# protection_and_ch.net
KiCad netlist of a schematic drawn in EAGLE
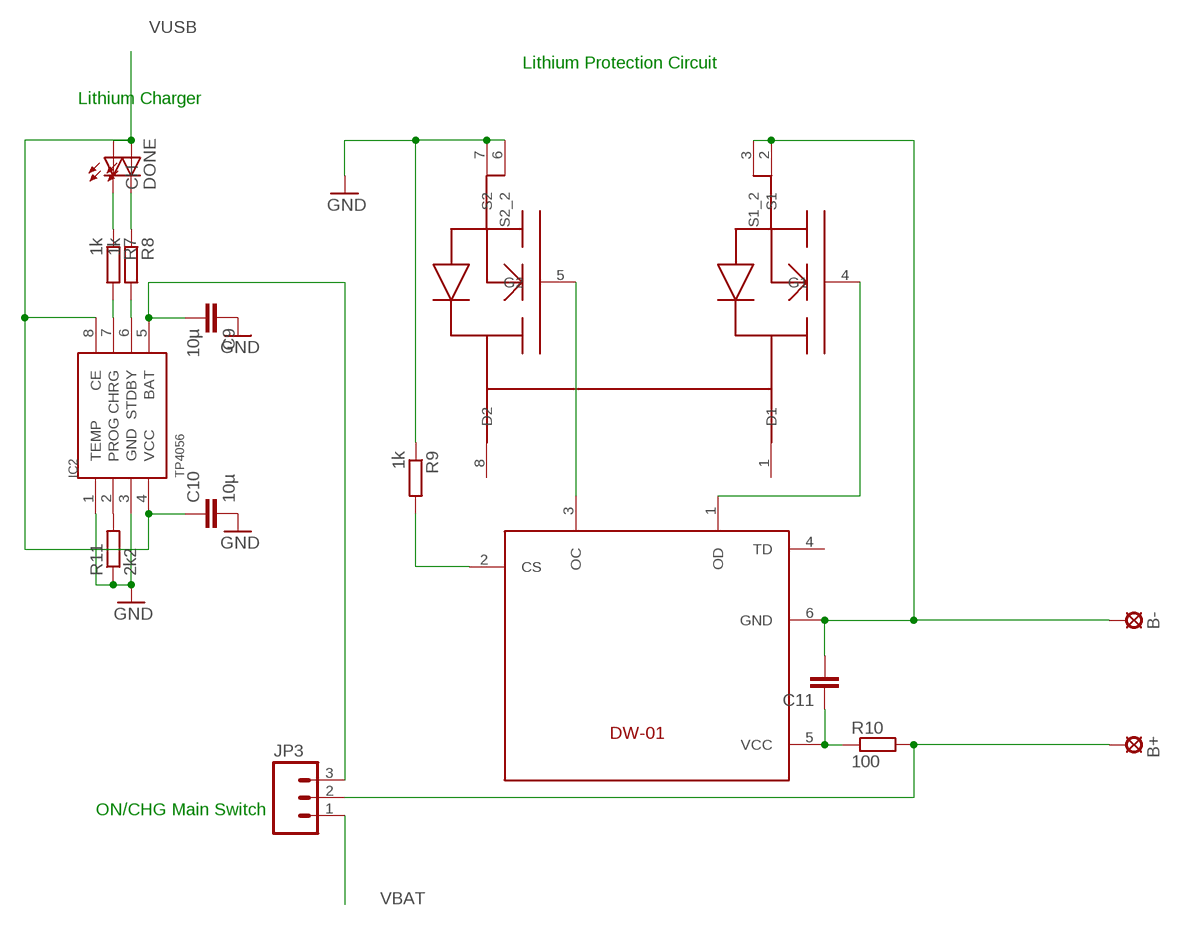
[diagram p0: schematic, sheet 1]

(export (version "E")
  (design (tool "Eeschema 10.0.6"))
  (components
    (comp (ref "B+")
      (value "LSP10")
      (footprint "eagle-import:LSP10")
      (libsource (lib "eagle-import") (part "LSP10"))
    )
    (comp (ref "B-")
      (value "LSP10")
      (footprint "eagle-import:LSP10")
      (libsource (lib "eagle-import") (part "LSP10"))
    )
    (comp (ref "C9")
      (value "10µ")
      (footprint "eagle-import:C0805K")
      (libsource (lib "eagle-import") (part "C-EUC0805K"))
    )
    (comp (ref "C10")
      (value "10µ")
      (footprint "eagle-import:C0805K")
      (libsource (lib "eagle-import") (part "C-EUC0805K"))
    )
    (comp (ref "C11")
      (value "C-EUC0603")
      (footprint "eagle-import:C0603")
      (libsource (lib "eagle-import") (part "C-EUC0603"))
    )
    (comp (ref "CH")
      (value "LEDCHIP-LED0805")
      (footprint "eagle-import:CHIP-LED0805")
      (libsource (lib "eagle-import") (part "LEDCHIP-LED0805"))
    )
    (comp (ref "DONE")
      (value "LEDCHIP-LED0805")
      (footprint "eagle-import:CHIP-LED0805")
      (libsource (lib "eagle-import") (part "LEDCHIP-LED0805"))
    )
    (comp (ref "IC2")
      (value "TP4056")
      (footprint "eagle-import:SOP-8")
      (libsource (lib "eagle-import") (part "TP4056"))
    )
    (comp (ref "JP3")
      (value "M03PTH")
      (footprint "eagle-import:1X03")
      (libsource (lib "eagle-import") (part "M03PTH"))
    )
    (comp (ref "R7")
      (value "1k")
      (footprint "eagle-import:R0603")
      (libsource (lib "eagle-import") (part "R-EU_R0603"))
    )
    (comp (ref "R8")
      (value "1k")
      (footprint "eagle-import:R0603")
      (libsource (lib "eagle-import") (part "R-EU_R0603"))
    )
    (comp (ref "R9")
      (value "1k")
      (footprint "eagle-import:R0603")
      (libsource (lib "eagle-import") (part "R-EU_R0603"))
    )
    (comp (ref "R10")
      (value "100")
      (footprint "eagle-import:R0603")
      (libsource (lib "eagle-import") (part "R-EU_R0603"))
    )
    (comp (ref "R11")
      (value "2k2")
      (footprint "eagle-import:R0603")
      (libsource (lib "eagle-import") (part "R-EU_R0603"))
    )
    (comp (ref "U$1")
      (value "DW-01")
      (footprint "eagle-import:SOT23-6")
      (libsource (lib "eagle-import") (part "DW-01"))
    )
    (comp (ref "U$4")
      (value "8205A")
      (footprint "eagle-import:TSSOP8")
      (libsource (lib "eagle-import") (part "8205A"))
    )
  )
  (nets
    (net (code "1") (name "/VBAT") (class "Default")
      (node (ref "B+") (pin "MP") (pinfunction "MP_MP") (pintype "passive"))
      (node (ref "JP3") (pin "1") (pinfunction "1_1") (pintype "passive"))
      (node (ref "JP3") (pin "2") (pinfunction "2_2") (pintype "passive"))
      (node (ref "R10") (pin "2") (pinfunction "2_2") (pintype "passive"))
    )
    (net (code "2") (name "/VUSB") (class "Default")
      (node (ref "C10") (pin "1") (pinfunction "1_1") (pintype "passive"))
      (node (ref "CH") (pin "A") (pinfunction "A_A") (pintype "passive"))
      (node (ref "DONE") (pin "A") (pinfunction "A_A") (pintype "passive"))
      (node (ref "IC2") (pin "4") (pinfunction "VCC_4") (pintype "bidirectional"))
      (node (ref "IC2") (pin "8") (pinfunction "CE_8") (pintype "bidirectional"))
    )
    (net (code "3") (name "GND") (class "Default")
      (node (ref "C10") (pin "2") (pinfunction "2_2") (pintype "passive"))
      (node (ref "C9") (pin "1") (pinfunction "1_1") (pintype "passive"))
      (node (ref "IC2") (pin "1") (pinfunction "TEMP_1") (pintype "bidirectional"))
      (node (ref "IC2") (pin "3") (pinfunction "GND_3") (pintype "bidirectional"))
      (node (ref "R11") (pin "1") (pinfunction "1_1") (pintype "passive"))
      (node (ref "R9") (pin "1") (pinfunction "1_1") (pintype "passive"))
      (node (ref "U$4") (pin "6") (pinfunction "S2_2_6") (pintype "bidirectional"))
      (node (ref "U$4") (pin "7") (pinfunction "S2_7") (pintype "bidirectional"))
    )
    (net (code "4") (name "Net-(CH-PadC)") (class "Default")
      (node (ref "CH") (pin "C") (pinfunction "C_C") (pintype "passive"))
      (node (ref "R7") (pin "1") (pinfunction "1_1") (pintype "passive"))
    )
    (net (code "5") (name "Net-(DONE-PadC)") (class "Default")
      (node (ref "DONE") (pin "C") (pinfunction "C_C") (pintype "passive"))
      (node (ref "R8") (pin "1") (pinfunction "1_1") (pintype "passive"))
    )
    (net (code "6") (name "Net-(IC2-BAT)") (class "Default")
      (node (ref "C9") (pin "2") (pinfunction "2_2") (pintype "passive"))
      (node (ref "IC2") (pin "5") (pinfunction "BAT_5") (pintype "bidirectional"))
      (node (ref "JP3") (pin "3") (pinfunction "3_3") (pintype "passive"))
    )
    (net (code "7") (name "Net-(IC2-CHRG)") (class "Default")
      (node (ref "IC2") (pin "7") (pinfunction "CHRG_7") (pintype "bidirectional"))
      (node (ref "R7") (pin "2") (pinfunction "2_2") (pintype "passive"))
    )
    (net (code "8") (name "Net-(IC2-PROG)") (class "Default")
      (node (ref "IC2") (pin "2") (pinfunction "PROG_2") (pintype "bidirectional"))
      (node (ref "R11") (pin "2") (pinfunction "2_2") (pintype "passive"))
    )
    (net (code "9") (name "Net-(IC2-STDBY)") (class "Default")
      (node (ref "IC2") (pin "6") (pinfunction "STDBY_6") (pintype "bidirectional"))
      (node (ref "R8") (pin "2") (pinfunction "2_2") (pintype "passive"))
    )
    (net (code "10") (name "Net-(U$1-CS)") (class "Default")
      (node (ref "R9") (pin "2") (pinfunction "2_2") (pintype "passive"))
      (node (ref "U$1") (pin "2") (pinfunction "CS_2") (pintype "bidirectional"))
    )
    (net (code "11") (name "Net-(U$1-GND)") (class "Default")
      (node (ref "B-") (pin "MP") (pinfunction "MP_MP") (pintype "passive"))
      (node (ref "C11") (pin "2") (pinfunction "2_2") (pintype "passive"))
      (node (ref "U$1") (pin "6") (pinfunction "GND_6") (pintype "bidirectional"))
      (node (ref "U$4") (pin "2") (pinfunction "S1_2") (pintype "bidirectional"))
      (node (ref "U$4") (pin "3") (pinfunction "S1_2_3") (pintype "bidirectional"))
    )
    (net (code "12") (name "Net-(U$1-OC)") (class "Default")
      (node (ref "U$1") (pin "3") (pinfunction "OC_3") (pintype "bidirectional"))
      (node (ref "U$4") (pin "5") (pinfunction "G2_5") (pintype "bidirectional"))
    )
    (net (code "13") (name "Net-(U$1-OD)") (class "Default")
      (node (ref "U$1") (pin "1") (pinfunction "OD_1") (pintype "bidirectional"))
      (node (ref "U$4") (pin "4") (pinfunction "G1_4") (pintype "bidirectional"))
    )
    (net (code "14") (name "Net-(U$1-VCC)") (class "Default")
      (node (ref "C11") (pin "1") (pinfunction "1_1") (pintype "passive"))
      (node (ref "R10") (pin "1") (pinfunction "1_1") (pintype "passive"))
      (node (ref "U$1") (pin "5") (pinfunction "VCC_5") (pintype "bidirectional"))
    )
    (net (code "15") (name "unconnected-(U$1-TD-Pad4)") (class "Default")
      (node (ref "U$1") (pin "4") (pinfunction "TD_4") (pintype "bidirectional"))
    )
    (net (code "16") (name "unconnected-(U$4-D1-Pad1)") (class "Default")
      (node (ref "U$4") (pin "1") (pinfunction "D1_1") (pintype "bidirectional"))
    )
    (net (code "17") (name "unconnected-(U$4-D2-Pad8)") (class "Default")
      (node (ref "U$4") (pin "8") (pinfunction "D2_8") (pintype "bidirectional"))
    )
  )
)
